# Lighthouse.net
KiCad netlist of a schematic drawn in EAGLE
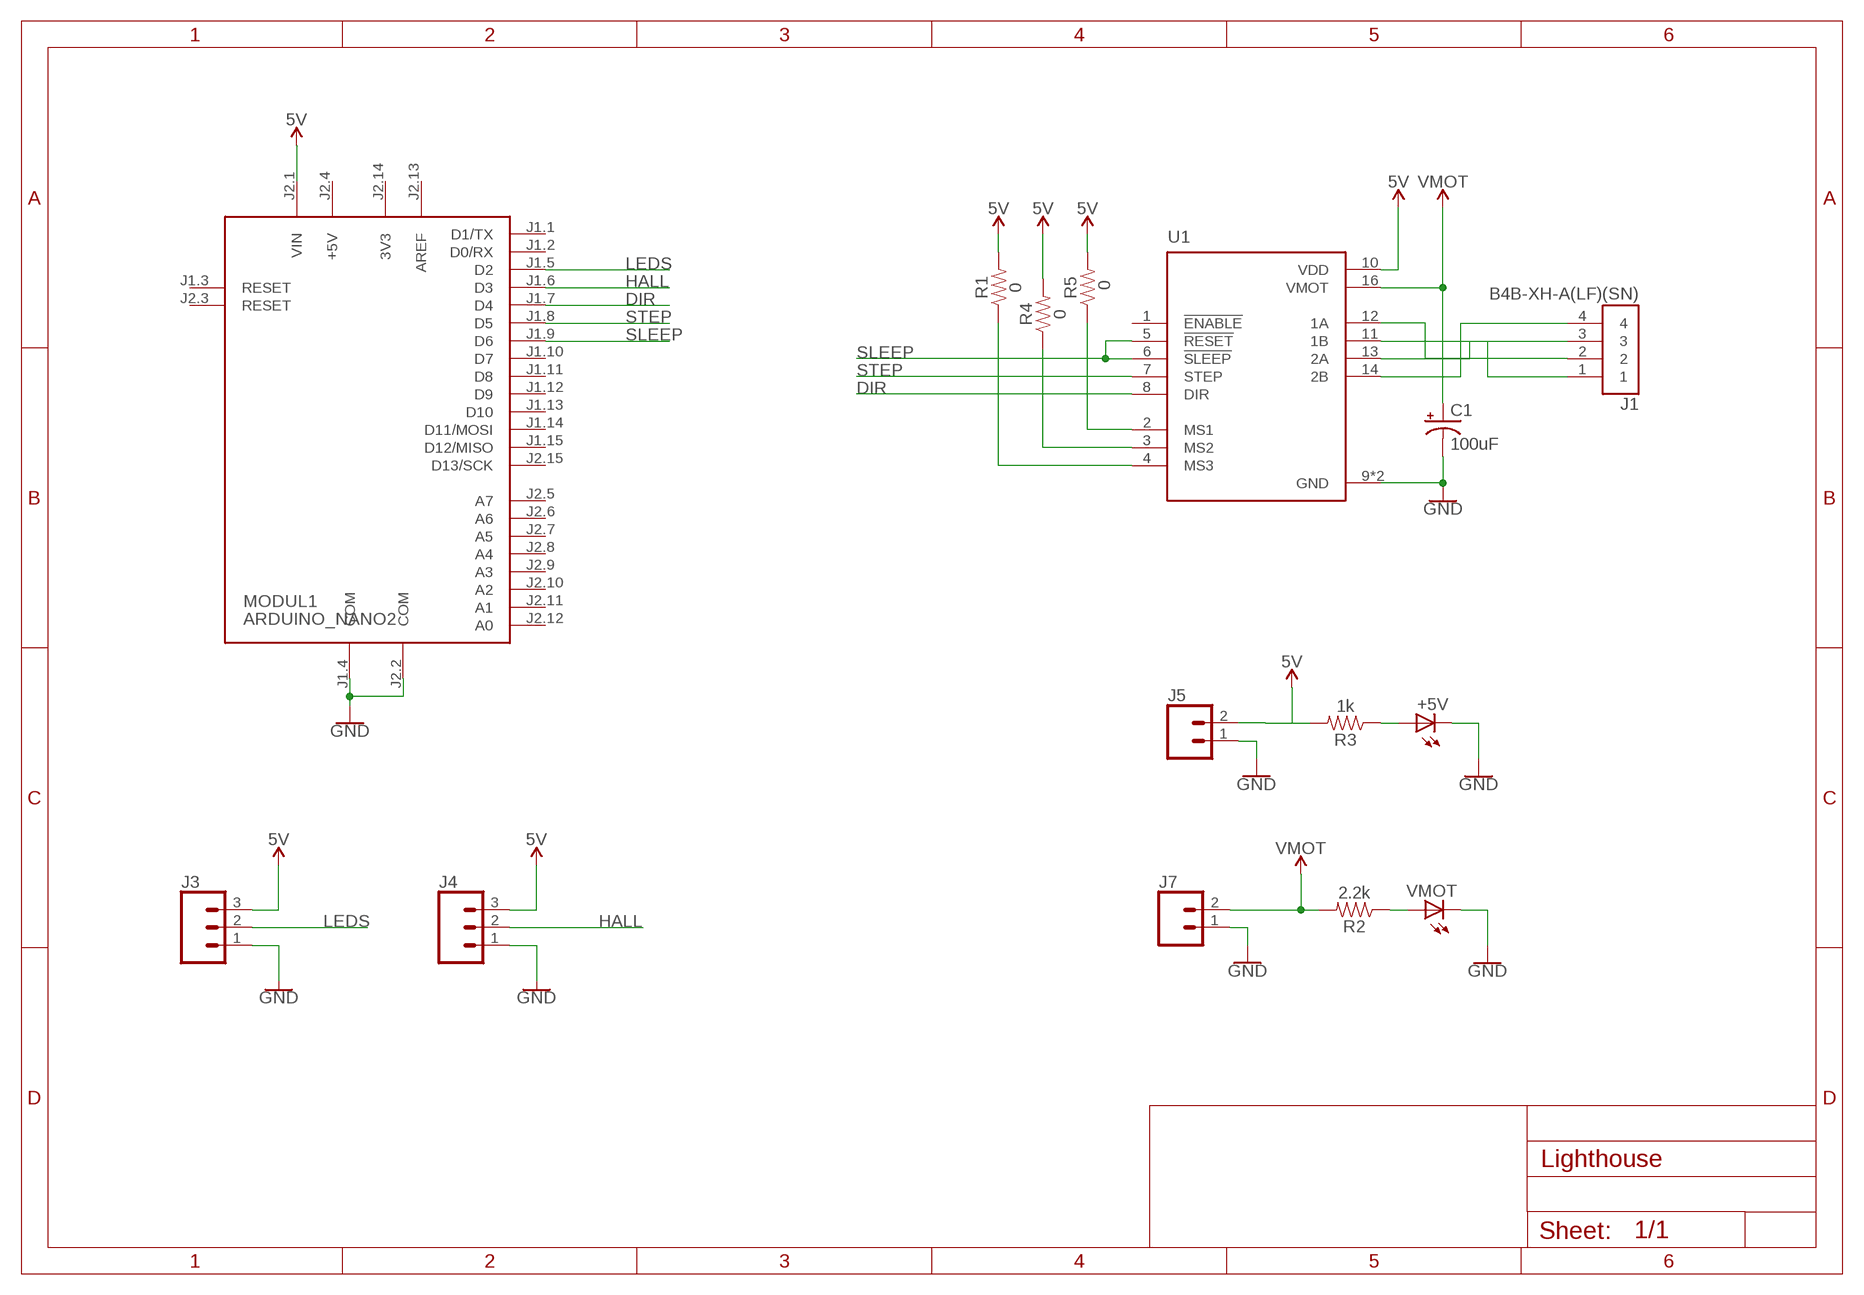
[diagram p0: schematic, sheet 1]

(export (version "E")
  (design (tool "Eeschema 10.0.6"))
  (components
    (comp (ref "+5V")
      (value "LEDP-LCC-2")
      (footprint "eagle-import:P-LCC-2")
      (libsource (lib "eagle-import") (part "LEDP-LCC-2"))
    )
    (comp (ref "C1")
      (value "100uF")
      (footprint "eagle-import:PANASONIC_D")
      (libsource (lib "eagle-import") (part "100UF-POLAR-25V-20%(ELEC)"))
    )
    (comp (ref "J1")
      (value "B4B-XH-A(LF)(SN)")
      (footprint "eagle-import:JST_B4B-XH-A(LF)(SN)")
      (fields (field (name "MF") "JST Sales"))
      (libsource (lib "eagle-import") (part "B4B-XH-A(LF)(SN)"))
    )
    (comp (ref "J3")
      (value "CONN_03SCREW")
      (footprint "eagle-import:SCREWTERMINAL-3.5MM-3")
      (libsource (lib "eagle-import") (part "CONN_03SCREW"))
    )
    (comp (ref "J4")
      (value "CONN_03SCREW")
      (footprint "eagle-import:SCREWTERMINAL-3.5MM-3")
      (libsource (lib "eagle-import") (part "CONN_03SCREW"))
    )
    (comp (ref "J5")
      (value "CONN_025MM")
      (footprint "eagle-import:SCREWTERMINAL-5MM-2")
      (libsource (lib "eagle-import") (part "CONN_025MM"))
    )
    (comp (ref "J7")
      (value "CONN_025MM")
      (footprint "eagle-import:SCREWTERMINAL-5MM-2")
      (libsource (lib "eagle-import") (part "CONN_025MM"))
    )
    (comp (ref "MODUL1")
      (value "ARDUINO_NANO2")
      (footprint "eagle-import:ARDUINO_NANO2")
      (libsource (lib "eagle-import") (part "ARDUINO_NANO2"))
    )
    (comp (ref "R1")
      (value "0")
      (footprint "eagle-import:1206")
      (libsource (lib "eagle-import") (part "RESISTOR1206"))
    )
    (comp (ref "R2")
      (value "2.2k")
      (footprint "eagle-import:1206")
      (libsource (lib "eagle-import") (part "RESISTOR1206"))
    )
    (comp (ref "R3")
      (value "1k")
      (footprint "eagle-import:1206")
      (libsource (lib "eagle-import") (part "RESISTOR1206"))
    )
    (comp (ref "R4")
      (value "0")
      (footprint "eagle-import:1206")
      (libsource (lib "eagle-import") (part "RESISTOR1206"))
    )
    (comp (ref "R5")
      (value "0")
      (footprint "eagle-import:1206")
      (libsource (lib "eagle-import") (part "RESISTOR1206"))
    )
    (comp (ref "U1")
      (value "A4988_STEPPER_MOTOR_DRIVER_CARRIER")
      (footprint "eagle-import:MODULE_A4988_STEPPER_MOTOR_DRIVER_CARRIER")
      (fields (field (name "MF") "Pololu") (field (name "MP") "A4988 STEPPER MOTOR DRIVER CARRIER"))
      (libsource (lib "eagle-import") (part "A4988_STEPPER_MOTOR_DRIVER_CARRIER"))
    )
    (comp (ref "VMOT")
      (value "LEDP-LCC-2")
      (footprint "eagle-import:P-LCC-2")
      (libsource (lib "eagle-import") (part "LEDP-LCC-2"))
    )
  )
  (nets
    (net (code "1") (name "/+5V") (class "Default")
      (node (ref "MODUL1") (pin "J2.4") (pinfunction "+5V_J2.4") (pintype "power_in"))
    )
    (net (code "2") (name "/3V3") (class "Default")
      (node (ref "MODUL1") (pin "J2.14") (pinfunction "3V3_J2.14") (pintype "power_in"))
    )
    (net (code "3") (name "/AREF") (class "Default")
      (node (ref "MODUL1") (pin "J2.13") (pinfunction "AREF_J2.13") (pintype "power_in"))
    )
    (net (code "4") (name "/DIR") (class "Default")
      (node (ref "MODUL1") (pin "J1.7") (pinfunction "D4_J1.7") (pintype "bidirectional"))
      (node (ref "U1") (pin "8") (pinfunction "DIR_8") (pintype "input"))
    )
    (net (code "5") (name "/HALL") (class "Default")
      (node (ref "J4") (pin "2") (pinfunction "2_2") (pintype "passive"))
      (node (ref "MODUL1") (pin "J1.6") (pinfunction "D3_J1.6") (pintype "bidirectional"))
    )
    (net (code "6") (name "/LEDS") (class "Default")
      (node (ref "J3") (pin "2") (pinfunction "2_2") (pintype "passive"))
      (node (ref "MODUL1") (pin "J1.5") (pinfunction "D2_J1.5") (pintype "bidirectional"))
    )
    (net (code "7") (name "/SLEEP") (class "Default")
      (node (ref "MODUL1") (pin "J1.9") (pinfunction "D6_J1.9") (pintype "bidirectional"))
      (node (ref "U1") (pin "5") (pinfunction "~{RESET}_5") (pintype "input"))
      (node (ref "U1") (pin "6") (pinfunction "~{SLEEP}_6") (pintype "input"))
    )
    (net (code "8") (name "/STEP") (class "Default")
      (node (ref "MODUL1") (pin "J1.8") (pinfunction "D5_J1.8") (pintype "bidirectional"))
      (node (ref "U1") (pin "7") (pinfunction "STEP_7") (pintype "input"))
    )
    (net (code "9") (name "5V") (class "Default")
      (node (ref "J3") (pin "3") (pinfunction "3_3") (pintype "passive"))
      (node (ref "J4") (pin "3") (pinfunction "3_3") (pintype "passive"))
      (node (ref "J5") (pin "2") (pinfunction "2_2") (pintype "passive"))
      (node (ref "MODUL1") (pin "J2.1") (pinfunction "VIN_J2.1") (pintype "power_in"))
      (node (ref "R1") (pin "2") (pinfunction "2_2") (pintype "passive"))
      (node (ref "R3") (pin "2") (pinfunction "2_2") (pintype "passive"))
      (node (ref "R4") (pin "2") (pinfunction "2_2") (pintype "passive"))
      (node (ref "R5") (pin "2") (pinfunction "2_2") (pintype "passive"))
      (node (ref "U1") (pin "10") (pinfunction "VDD_10") (pintype "power_in"))
    )
    (net (code "10") (name "GND") (class "Default")
      (node (ref "+5V") (pin "C") (pinfunction "C_C") (pintype "passive"))
      (node (ref "C1") (pin "-") (pinfunction "-_-") (pintype "passive"))
      (node (ref "J3") (pin "1") (pinfunction "1_1") (pintype "passive"))
      (node (ref "J4") (pin "1") (pinfunction "1_1") (pintype "passive"))
      (node (ref "J5") (pin "1") (pinfunction "1_1") (pintype "passive"))
      (node (ref "J7") (pin "1") (pinfunction "1_1") (pintype "passive"))
      (node (ref "MODUL1") (pin "J1.4") (pinfunction "COM_J1.4") (pintype "power_in"))
      (node (ref "MODUL1") (pin "J2.2") (pinfunction "COM_J2.2") (pintype "power_in"))
      (node (ref "U1") (pin "15") (pinfunction "GND_15") (pintype "power_in"))
      (node (ref "U1") (pin "9") (pinfunction "GND_9") (pintype "power_in"))
      (node (ref "VMOT") (pin "C") (pinfunction "C_C") (pintype "passive"))
    )
    (net (code "11") (name "Net-(+5V-PadA)") (class "Default")
      (node (ref "+5V") (pin "A") (pinfunction "A_A") (pintype "passive"))
      (node (ref "R3") (pin "1") (pinfunction "1_1") (pintype "passive"))
    )
    (net (code "12") (name "Net-(R2-Pad1)") (class "Default")
      (node (ref "R2") (pin "1") (pinfunction "1_1") (pintype "passive"))
      (node (ref "VMOT") (pin "A") (pinfunction "A_A") (pintype "passive"))
    )
    (net (code "13") (name "Net-(U1-1A)") (class "Default")
      (node (ref "J1") (pin "2") (pinfunction "2_2") (pintype "passive"))
      (node (ref "U1") (pin "12") (pinfunction "1A_12") (pintype "output"))
    )
    (net (code "14") (name "Net-(U1-1B)") (class "Default")
      (node (ref "J1") (pin "1") (pinfunction "1_1") (pintype "passive"))
      (node (ref "U1") (pin "11") (pinfunction "1B_11") (pintype "output"))
    )
    (net (code "15") (name "Net-(U1-2A)") (class "Default")
      (node (ref "J1") (pin "3") (pinfunction "3_3") (pintype "passive"))
      (node (ref "U1") (pin "13") (pinfunction "2A_13") (pintype "output"))
    )
    (net (code "16") (name "Net-(U1-2B)") (class "Default")
      (node (ref "J1") (pin "4") (pinfunction "4_4") (pintype "passive"))
      (node (ref "U1") (pin "14") (pinfunction "2B_14") (pintype "output"))
    )
    (net (code "17") (name "Net-(U1-MS1)") (class "Default")
      (node (ref "R5") (pin "1") (pinfunction "1_1") (pintype "passive"))
      (node (ref "U1") (pin "2") (pinfunction "MS1_2") (pintype "input"))
    )
    (net (code "18") (name "Net-(U1-MS2)") (class "Default")
      (node (ref "R4") (pin "1") (pinfunction "1_1") (pintype "passive"))
      (node (ref "U1") (pin "3") (pinfunction "MS2_3") (pintype "input"))
    )
    (net (code "19") (name "Net-(U1-MS3)") (class "Default")
      (node (ref "R1") (pin "1") (pinfunction "1_1") (pintype "passive"))
      (node (ref "U1") (pin "4") (pinfunction "MS3_4") (pintype "input"))
    )
    (net (code "20") (name "VMOT") (class "Default")
      (node (ref "C1") (pin "+") (pinfunction "+_+") (pintype "passive"))
      (node (ref "J7") (pin "2") (pinfunction "2_2") (pintype "passive"))
      (node (ref "R2") (pin "2") (pinfunction "2_2") (pintype "passive"))
      (node (ref "U1") (pin "16") (pinfunction "VMOT_16") (pintype "power_in"))
    )
    (net (code "21") (name "unconnected-(MODUL1-A0-PadJ2.12)") (class "Default")
      (node (ref "MODUL1") (pin "J2.12") (pinfunction "A0_J2.12") (pintype "bidirectional"))
    )
    (net (code "22") (name "unconnected-(MODUL1-A1-PadJ2.11)") (class "Default")
      (node (ref "MODUL1") (pin "J2.11") (pinfunction "A1_J2.11") (pintype "bidirectional"))
    )
    (net (code "23") (name "unconnected-(MODUL1-A2-PadJ2.10)") (class "Default")
      (node (ref "MODUL1") (pin "J2.10") (pinfunction "A2_J2.10") (pintype "bidirectional"))
    )
    (net (code "24") (name "unconnected-(MODUL1-A3-PadJ2.9)") (class "Default")
      (node (ref "MODUL1") (pin "J2.9") (pinfunction "A3_J2.9") (pintype "bidirectional"))
    )
    (net (code "25") (name "unconnected-(MODUL1-A4-PadJ2.8)") (class "Default")
      (node (ref "MODUL1") (pin "J2.8") (pinfunction "A4_J2.8") (pintype "bidirectional"))
    )
    (net (code "26") (name "unconnected-(MODUL1-A5-PadJ2.7)") (class "Default")
      (node (ref "MODUL1") (pin "J2.7") (pinfunction "A5_J2.7") (pintype "bidirectional"))
    )
    (net (code "27") (name "unconnected-(MODUL1-A6-PadJ2.6)") (class "Default")
      (node (ref "MODUL1") (pin "J2.6") (pinfunction "A6_J2.6") (pintype "bidirectional"))
    )
    (net (code "28") (name "unconnected-(MODUL1-A7-PadJ2.5)") (class "Default")
      (node (ref "MODUL1") (pin "J2.5") (pinfunction "A7_J2.5") (pintype "bidirectional"))
    )
    (net (code "29") (name "unconnected-(MODUL1-D0{slash}RX-PadJ1.2)") (class "Default")
      (node (ref "MODUL1") (pin "J1.2") (pinfunction "D0/RX_J1.2") (pintype "bidirectional"))
    )
    (net (code "30") (name "unconnected-(MODUL1-D1{slash}TX-PadJ1.1)") (class "Default")
      (node (ref "MODUL1") (pin "J1.1") (pinfunction "D1/TX_J1.1") (pintype "bidirectional"))
    )
    (net (code "31") (name "unconnected-(MODUL1-D7-PadJ1.10)") (class "Default")
      (node (ref "MODUL1") (pin "J1.10") (pinfunction "D7_J1.10") (pintype "bidirectional"))
    )
    (net (code "32") (name "unconnected-(MODUL1-D8-PadJ1.11)") (class "Default")
      (node (ref "MODUL1") (pin "J1.11") (pinfunction "D8_J1.11") (pintype "bidirectional"))
    )
    (net (code "33") (name "unconnected-(MODUL1-D9-PadJ1.12)") (class "Default")
      (node (ref "MODUL1") (pin "J1.12") (pinfunction "D9_J1.12") (pintype "bidirectional"))
    )
    (net (code "34") (name "unconnected-(MODUL1-D10-PadJ1.13)") (class "Default")
      (node (ref "MODUL1") (pin "J1.13") (pinfunction "D10_J1.13") (pintype "bidirectional"))
    )
    (net (code "35") (name "unconnected-(MODUL1-D11{slash}MOSI-PadJ1.14)") (class "Default")
      (node (ref "MODUL1") (pin "J1.14") (pinfunction "D11/MOSI_J1.14") (pintype "bidirectional"))
    )
    (net (code "36") (name "unconnected-(MODUL1-D12{slash}MISO-PadJ1.15)") (class "Default")
      (node (ref "MODUL1") (pin "J1.15") (pinfunction "D12/MISO_J1.15") (pintype "bidirectional"))
    )
    (net (code "37") (name "unconnected-(MODUL1-D13{slash}SCK-PadJ2.15)") (class "Default")
      (node (ref "MODUL1") (pin "J2.15") (pinfunction "D13/SCK_J2.15") (pintype "bidirectional"))
    )
    (net (code "38") (name "unconnected-(MODUL1-RESET-PadJ1.3)") (class "Default")
      (node (ref "MODUL1") (pin "J1.3") (pinfunction "RESET_J1.3") (pintype "bidirectional"))
    )
    (net (code "39") (name "unconnected-(MODUL1-RESET-PadJ2.3)") (class "Default")
      (node (ref "MODUL1") (pin "J2.3") (pinfunction "RESET_J2.3") (pintype "bidirectional"))
    )
    (net (code "40") (name "unconnected-(U1-~{ENABLE}-Pad1)") (class "Default")
      (node (ref "U1") (pin "1") (pinfunction "~{ENABLE}_1") (pintype "input"))
    )
  )
)
